# fw_adapter.net
KiCad netlist of a schematic drawn in EAGLE
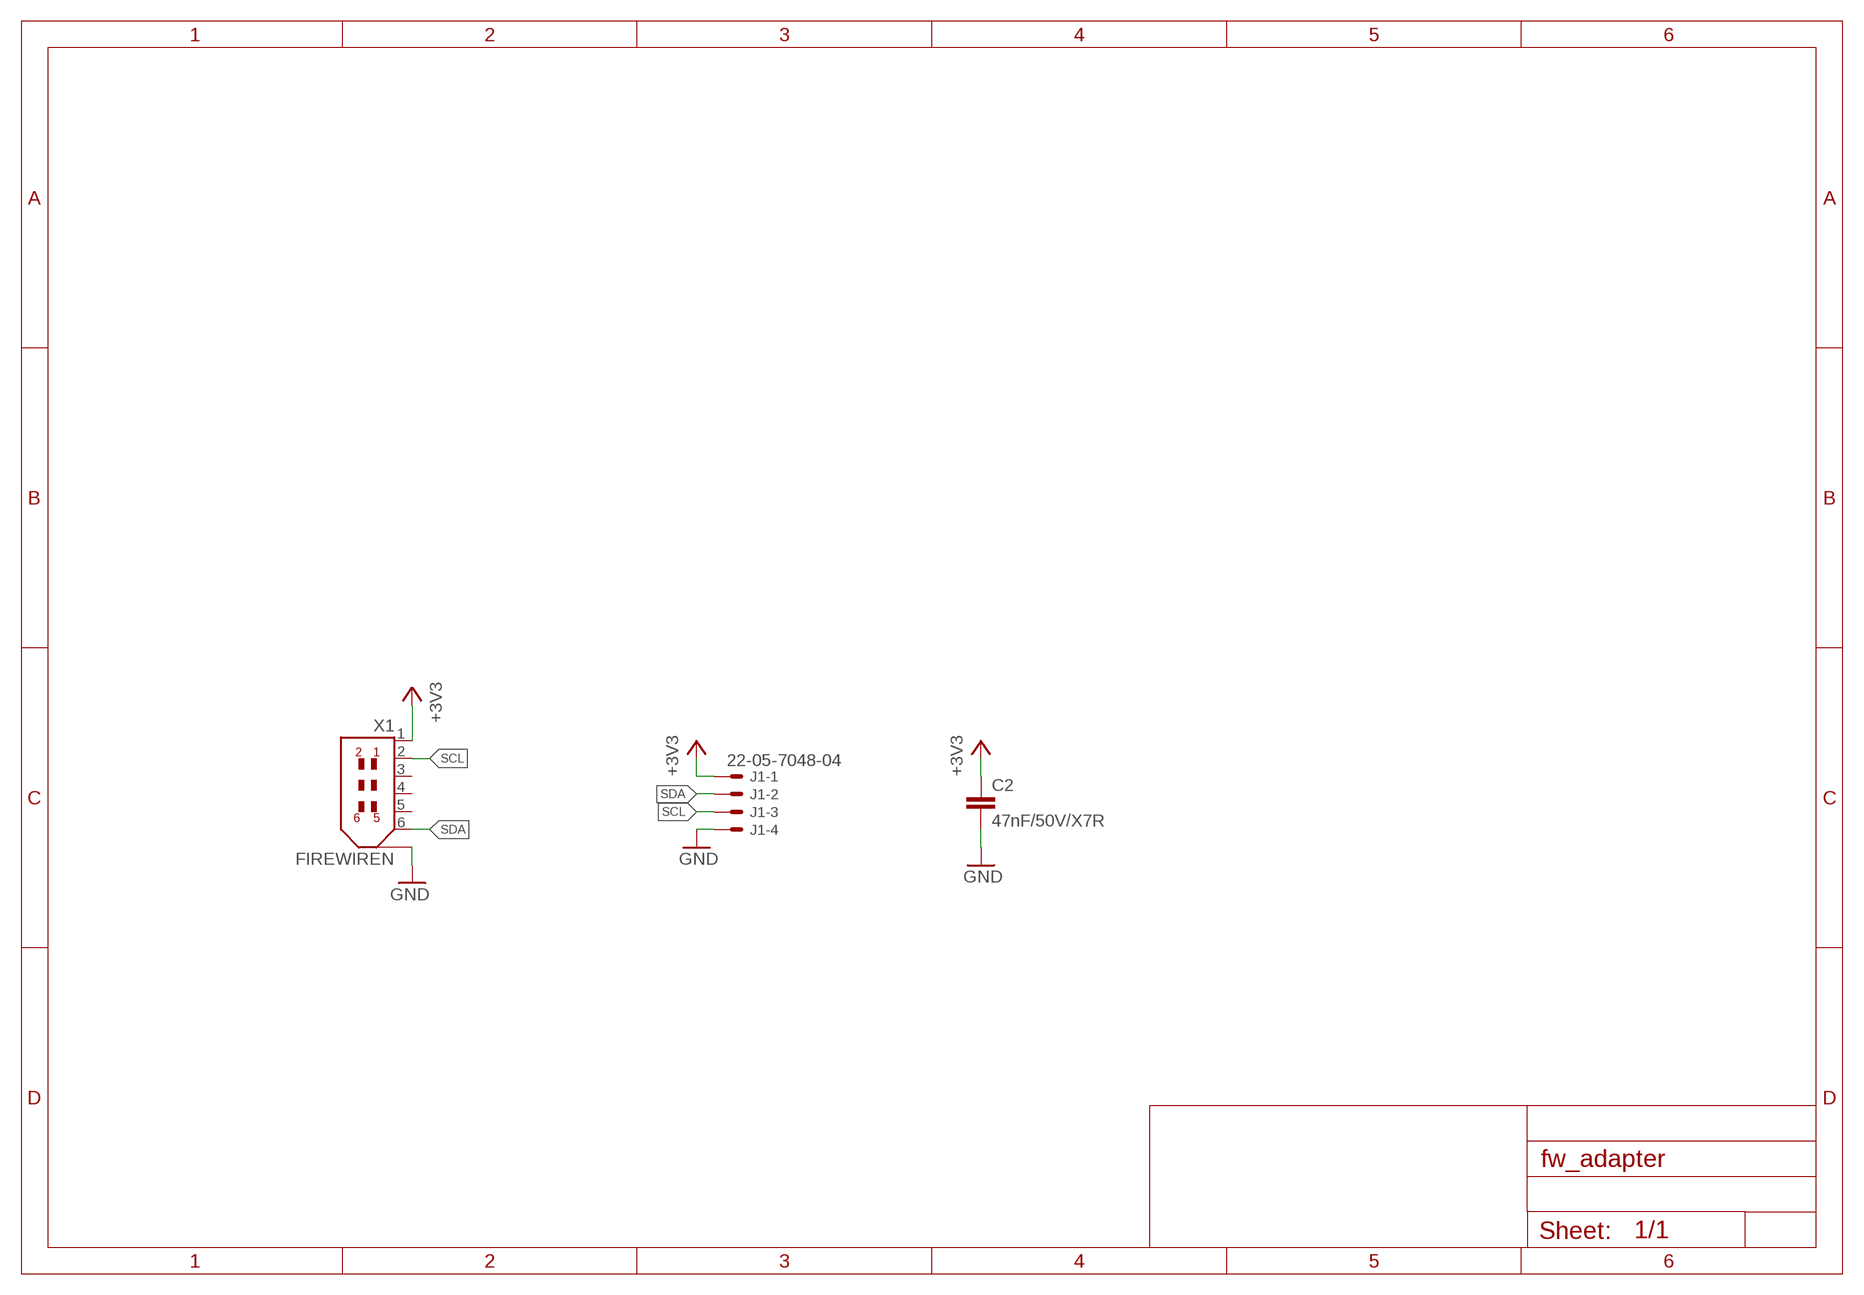
[diagram p0: schematic, sheet 1]

(export (version "E")
  (design (tool "Eeschema 10.0.6"))
  (components
    (comp (ref "C2")
      (value "47nF/50V/X7R")
      (footprint "eagle-import:C0603K")
      (libsource (lib "eagle-import") (part "C-EUC0603K"))
    )
    (comp (ref "J1")
      (value "22-05-7048-04")
      (footprint "eagle-import:7395-04")
      (libsource (lib "eagle-import") (part "22-?-0405-7048"))
    )
    (comp (ref "X1")
      (value "FIREWIREN")
      (footprint "eagle-import:IEEE1394_90DEG_PINS_NORMAL")
      (libsource (lib "eagle-import") (part "FIREWIREN"))
    )
  )
  (nets
    (net (code "1") (name "+3V3") (class "Default")
      (node (ref "C2") (pin "1") (pinfunction "1_1") (pintype "passive"))
      (node (ref "J1") (pin "1") (pinfunction "S_1") (pintype "passive"))
      (node (ref "X1") (pin "1") (pinfunction "1_1") (pintype "passive"))
    )
    (net (code "2") (name "GND") (class "Default")
      (node (ref "C2") (pin "2") (pinfunction "2_2") (pintype "passive"))
      (node (ref "J1") (pin "4") (pinfunction "S_4") (pintype "passive"))
      (node (ref "X1") (pin "M1") (pinfunction "7_M1") (pintype "passive"))
      (node (ref "X1") (pin "M2") (pinfunction "7_M2") (pintype "passive"))
    )
    (net (code "3") (name "SCL") (class "Default")
      (node (ref "J1") (pin "3") (pinfunction "S_3") (pintype "passive"))
      (node (ref "X1") (pin "2") (pinfunction "2_2") (pintype "passive"))
    )
    (net (code "4") (name "SDA") (class "Default")
      (node (ref "J1") (pin "2") (pinfunction "S_2") (pintype "passive"))
      (node (ref "X1") (pin "6") (pinfunction "6_6") (pintype "passive"))
    )
    (net (code "5") (name "unconnected-(X1-Pad3)") (class "Default")
      (node (ref "X1") (pin "3") (pinfunction "3_3") (pintype "passive"))
    )
    (net (code "6") (name "unconnected-(X1-Pad4)") (class "Default")
      (node (ref "X1") (pin "4") (pinfunction "4_4") (pintype "passive"))
    )
    (net (code "7") (name "unconnected-(X1-Pad5)") (class "Default")
      (node (ref "X1") (pin "5") (pinfunction "5_5") (pintype "passive"))
    )
  )
)
